# SCH_Sherap_2021-11-23.net
KiCad netlist of a schematic drawn in EasyEDA
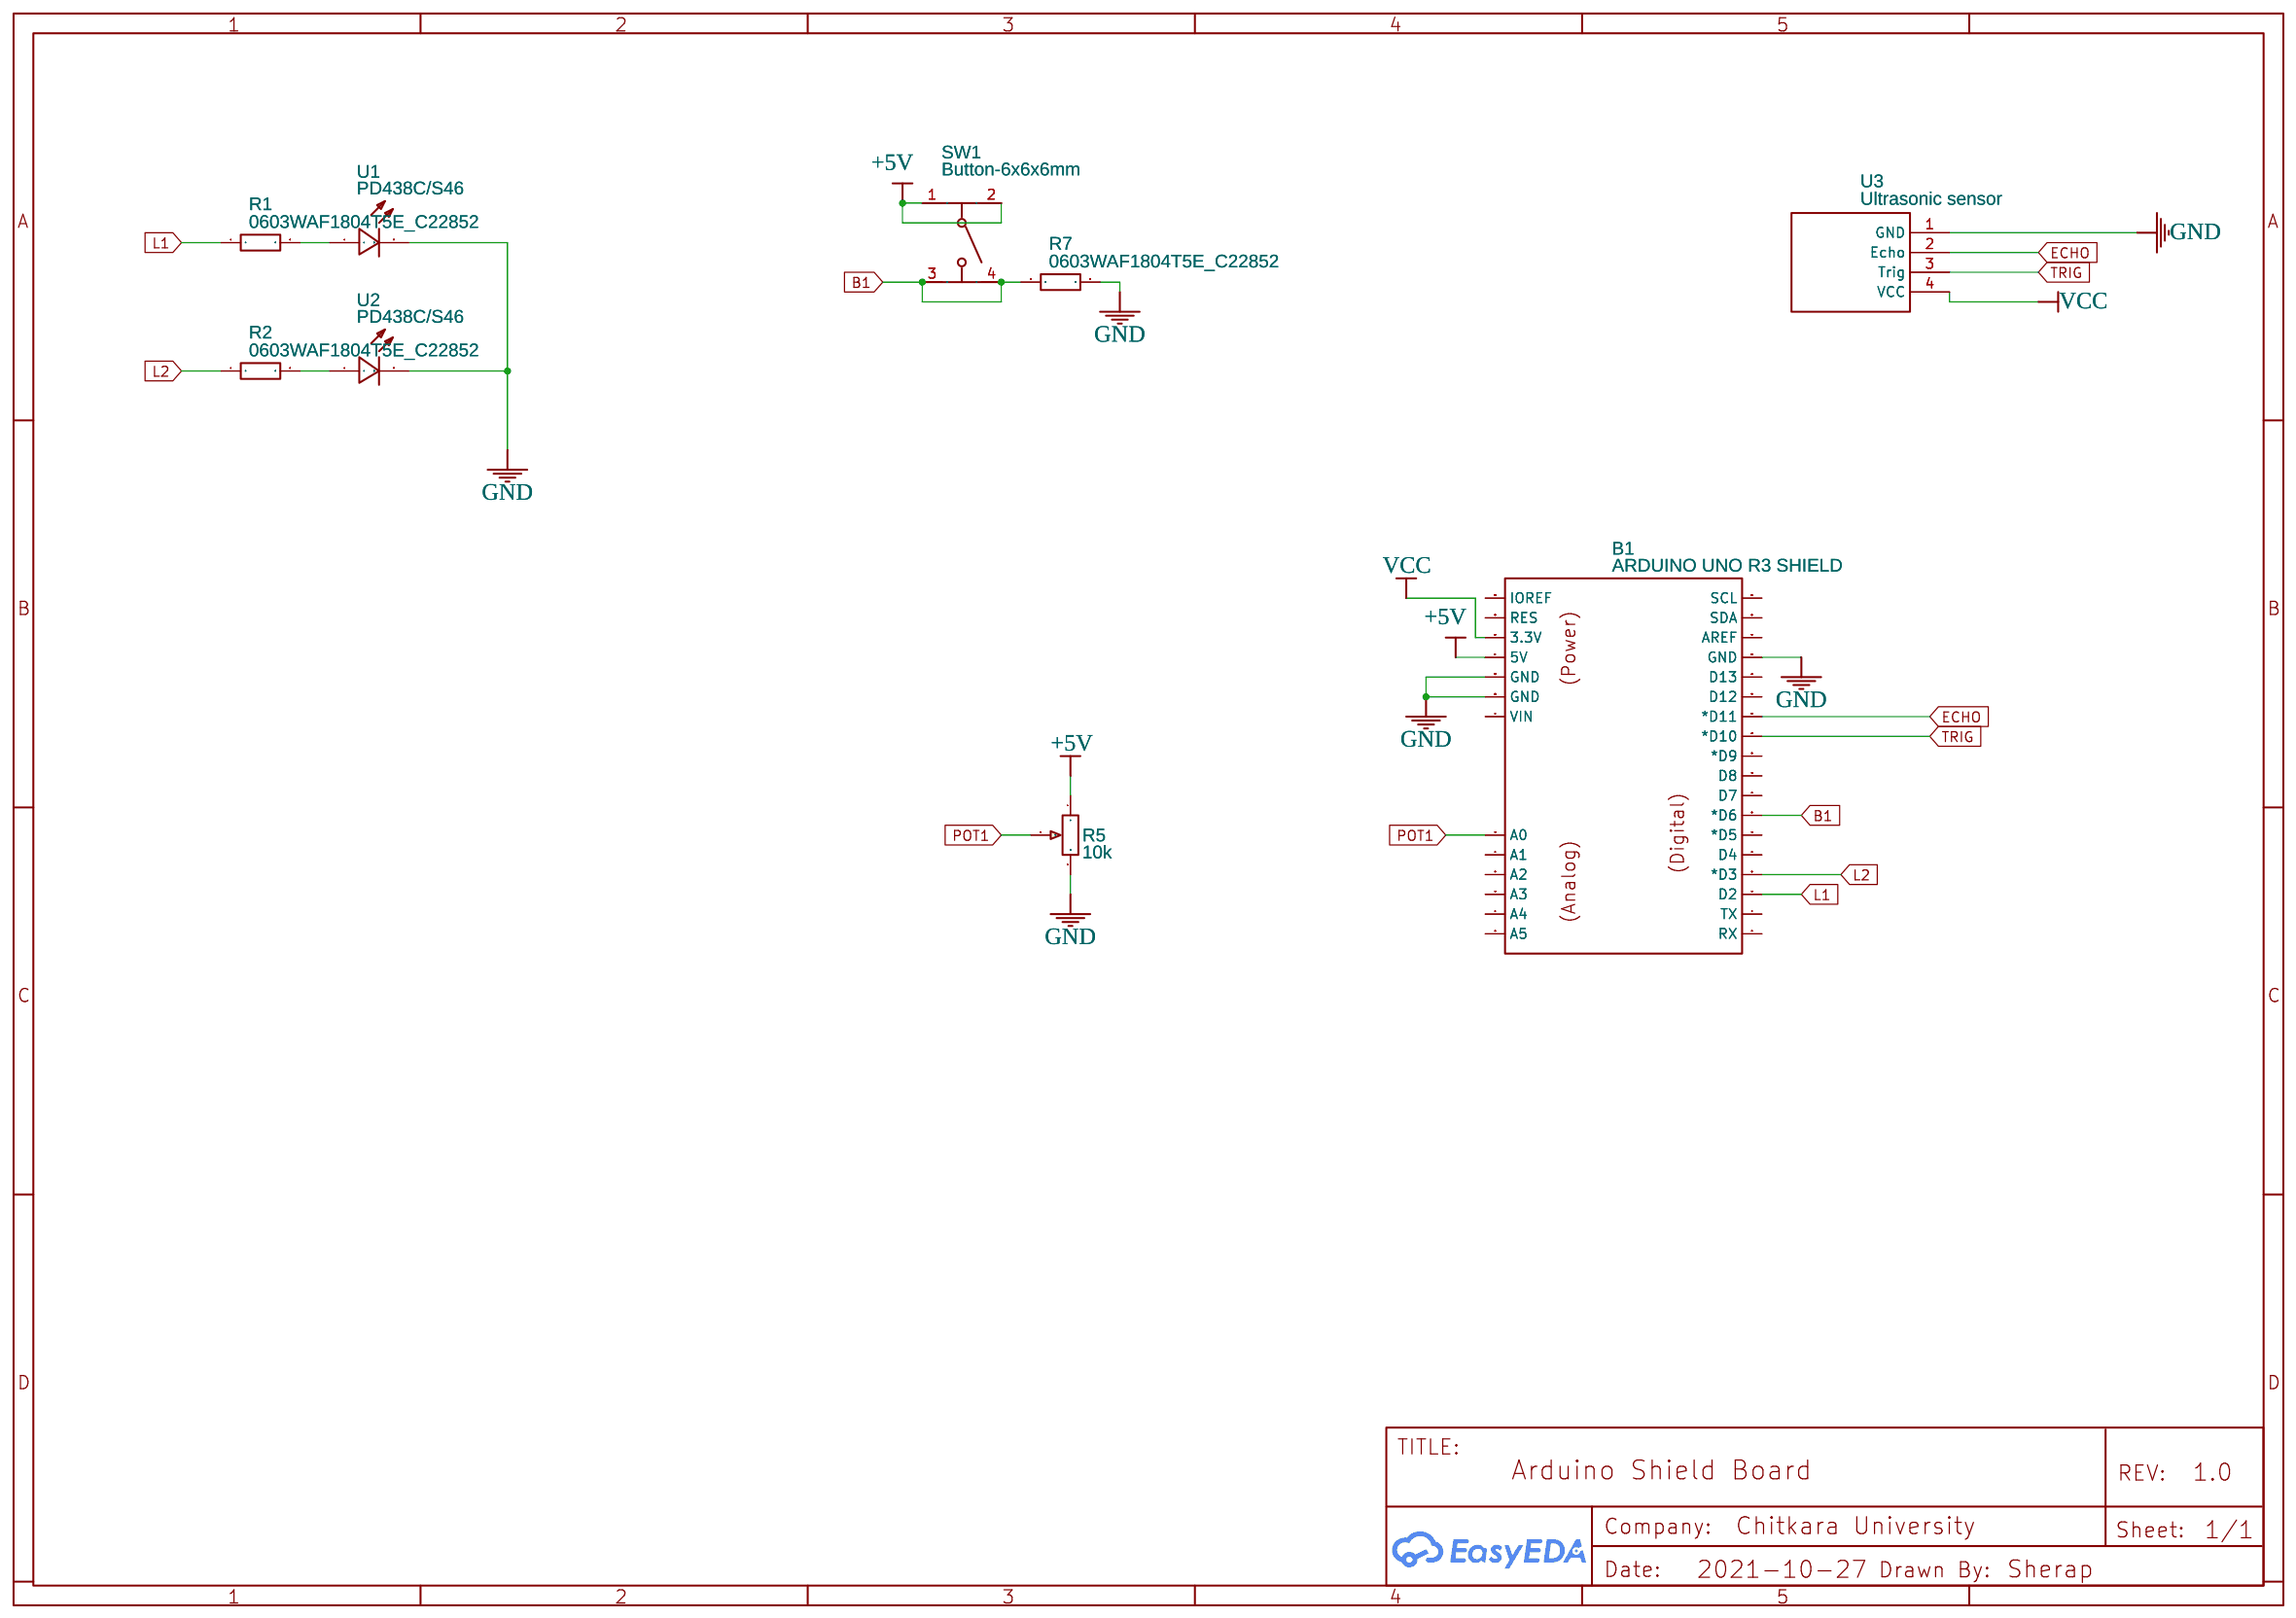
[diagram p0: schematic sheet]

(export (version "E")
  (design (tool "Eeschema 10.0.6"))
  (components
    (comp (ref "B1")
      (value "ARDUINO UNO R3 SHIELD")
      (fields (field (name "Manufacturer") "?"))
      (libsource (lib "") (part "ARDUINO UNO R3 SHIELD"))
    )
    (comp (ref "R1")
      (value "0603WAF1804T5E_C22852")
      (fields
        (field (name "BOM_Manufacturer Part") "0603WAF1804T5E")
        (field (name "BOM_Supplier Part") "C22852")
      )
      (libsource (lib "") (part "0603WAF1804T5E_C22852"))
    )
    (comp (ref "R2")
      (value "0603WAF1804T5E_C22852")
      (fields
        (field (name "BOM_Manufacturer Part") "0603WAF1804T5E")
        (field (name "BOM_Supplier Part") "C22852")
      )
      (libsource (lib "") (part "0603WAF1804T5E_C22852"))
    )
    (comp (ref "R5")
      (value "10k")
      (fields
        (field (name "BOM_Manufacturer Part") "3362F-1-103LF")
        (field (name "BOM_Supplier Part") "3362F-1-103LF-ND")
      )
      (libsource (lib "") (part "3362F-1-103LF"))
    )
    (comp (ref "R7")
      (value "0603WAF1804T5E_C22852")
      (fields
        (field (name "BOM_Manufacturer Part") "0603WAF1804T5E")
        (field (name "BOM_Supplier Part") "C22852")
      )
      (libsource (lib "") (part "0603WAF1804T5E_C22852"))
    )
    (comp (ref "SW1")
      (value "Button-6x6x6mm")
      (fields
        (field (name "BOM_Manufacturer Part") "Switch,6*6*6Plastic head,260G, 0.25mm,Straight line")
        (field (name "BOM_Supplier Part") "C71836")
      )
      (libsource (lib "") (part "Button-6x6x6mm"))
    )
    (comp (ref "U1")
      (value "PD438C/S46")
      (fields (field (name "BOM_Supplier Part") "C146238"))
      (libsource (lib "") (part "PD438C/S46"))
    )
    (comp (ref "U2")
      (value "PD438C/S46")
      (fields (field (name "BOM_Supplier Part") "C146238"))
      (libsource (lib "") (part "PD438C/S46"))
    )
    (comp (ref "U3") (value "Ultrasonic sensor") (libsource (lib "") (part "Ultrasonic sensor")))
  )
  (nets
    (net (code "1") (name "+5V") (class "Default")
      (node (ref "B1") (pin "5V") (pinfunction "5V_5V") (pintype "unspecified"))
      (node (ref "R5") (pin "1") (pinfunction "1_1") (pintype "input"))
      (node (ref "SW1") (pin "1") (pinfunction "1_1") (pintype "unspecified"))
      (node (ref "SW1") (pin "2") (pinfunction "2_2") (pintype "unspecified"))
    )
    (net (code "2") (name "B1") (class "Default")
      (node (ref "B1") (pin "D6") (pinfunction "*D6_D6") (pintype "unspecified"))
      (node (ref "R7") (pin "1") (pinfunction "1_1") (pintype "input"))
      (node (ref "SW1") (pin "3") (pinfunction "3_3") (pintype "unspecified"))
      (node (ref "SW1") (pin "4") (pinfunction "4_4") (pintype "unspecified"))
    )
    (net (code "3") (name "ECHO") (class "Default")
      (node (ref "B1") (pin "D11") (pinfunction "*D11_D11") (pintype "unspecified"))
      (node (ref "U3") (pin "2") (pinfunction "Echo_2") (pintype "unspecified"))
    )
    (net (code "4") (name "GND") (class "Default")
      (node (ref "B1") (pin "GND@0") (pinfunction "GND_GND@0") (pintype "unspecified"))
      (node (ref "B1") (pin "GND@1") (pinfunction "GND_GND@1") (pintype "unspecified"))
      (node (ref "B1") (pin "GND@2") (pinfunction "GND_GND@2") (pintype "unspecified"))
      (node (ref "R5") (pin "3") (pinfunction "3_3") (pintype "input"))
      (node (ref "R7") (pin "2") (pinfunction "2_2") (pintype "input"))
      (node (ref "U1") (pin "2") (pinfunction "C_2") (pintype "unspecified"))
      (node (ref "U2") (pin "2") (pinfunction "C_2") (pintype "unspecified"))
      (node (ref "U3") (pin "1") (pinfunction "GND_1") (pintype "unspecified"))
    )
    (net (code "5") (name "L1") (class "Default")
      (node (ref "B1") (pin "D2") (pinfunction "D2_D2") (pintype "unspecified"))
      (node (ref "R1") (pin "1") (pinfunction "1_1") (pintype "input"))
    )
    (net (code "6") (name "L2") (class "Default")
      (node (ref "B1") (pin "D3") (pinfunction "*D3_D3") (pintype "unspecified"))
      (node (ref "R2") (pin "1") (pinfunction "1_1") (pintype "input"))
    )
    (net (code "7") (name "Net-(U1-A)") (class "Default")
      (node (ref "R1") (pin "2") (pinfunction "2_2") (pintype "input"))
      (node (ref "U1") (pin "1") (pinfunction "A_1") (pintype "unspecified"))
    )
    (net (code "8") (name "Net-(U2-A)") (class "Default")
      (node (ref "R2") (pin "2") (pinfunction "2_2") (pintype "input"))
      (node (ref "U2") (pin "1") (pinfunction "A_1") (pintype "unspecified"))
    )
    (net (code "9") (name "POT1") (class "Default")
      (node (ref "B1") (pin "A0") (pinfunction "A0_A0") (pintype "unspecified"))
      (node (ref "R5") (pin "2") (pinfunction "2_2") (pintype "input"))
    )
    (net (code "10") (name "TRIG") (class "Default")
      (node (ref "B1") (pin "D10") (pinfunction "*D10_D10") (pintype "unspecified"))
      (node (ref "U3") (pin "3") (pinfunction "Trig_3") (pintype "unspecified"))
    )
    (net (code "11") (name "VCC") (class "Default")
      (node (ref "B1") (pin "3.3V") (pinfunction "3.3V_3.3V") (pintype "unspecified"))
      (node (ref "U3") (pin "4") (pinfunction "VCC_4") (pintype "unspecified"))
    )
    (net (code "12") (name "unconnected-(B1-*D5-PadD5)") (class "Default")
      (node (ref "B1") (pin "D5") (pinfunction "*D5_D5") (pintype "unspecified"))
    )
    (net (code "13") (name "unconnected-(B1-*D9-PadD9)") (class "Default")
      (node (ref "B1") (pin "D9") (pinfunction "*D9_D9") (pintype "unspecified"))
    )
    (net (code "14") (name "unconnected-(B1-PadA1)") (class "Default")
      (node (ref "B1") (pin "A1") (pinfunction "A1_A1") (pintype "unspecified"))
    )
    (net (code "15") (name "unconnected-(B1-PadA2)") (class "Default")
      (node (ref "B1") (pin "A2") (pinfunction "A2_A2") (pintype "unspecified"))
    )
    (net (code "16") (name "unconnected-(B1-PadA3)") (class "Default")
      (node (ref "B1") (pin "A3") (pinfunction "A3_A3") (pintype "unspecified"))
    )
    (net (code "17") (name "unconnected-(B1-PadA4)") (class "Default")
      (node (ref "B1") (pin "A4") (pinfunction "A4_A4") (pintype "unspecified"))
    )
    (net (code "18") (name "unconnected-(B1-PadA5)") (class "Default")
      (node (ref "B1") (pin "A5") (pinfunction "A5_A5") (pintype "unspecified"))
    )
    (net (code "19") (name "unconnected-(B1-PadAREF)") (class "Default")
      (node (ref "B1") (pin "AREF") (pinfunction "AREF_AREF") (pintype "unspecified"))
    )
    (net (code "20") (name "unconnected-(B1-PadD4)") (class "Default")
      (node (ref "B1") (pin "D4") (pinfunction "D4_D4") (pintype "unspecified"))
    )
    (net (code "21") (name "unconnected-(B1-PadD7)") (class "Default")
      (node (ref "B1") (pin "D7") (pinfunction "D7_D7") (pintype "unspecified"))
    )
    (net (code "22") (name "unconnected-(B1-PadD8)") (class "Default")
      (node (ref "B1") (pin "D8") (pinfunction "D8_D8") (pintype "unspecified"))
    )
    (net (code "23") (name "unconnected-(B1-PadD12)") (class "Default")
      (node (ref "B1") (pin "D12") (pinfunction "D12_D12") (pintype "unspecified"))
    )
    (net (code "24") (name "unconnected-(B1-PadD13)") (class "Default")
      (node (ref "B1") (pin "D13") (pinfunction "D13_D13") (pintype "unspecified"))
    )
    (net (code "25") (name "unconnected-(B1-PadIOREF)") (class "Default")
      (node (ref "B1") (pin "IOREF") (pinfunction "IOREF_IOREF") (pintype "unspecified"))
    )
    (net (code "26") (name "unconnected-(B1-PadRES)") (class "Default")
      (node (ref "B1") (pin "RES") (pinfunction "RES_RES") (pintype "unspecified"))
    )
    (net (code "27") (name "unconnected-(B1-PadRX)") (class "Default")
      (node (ref "B1") (pin "RX") (pinfunction "RX_RX") (pintype "unspecified"))
    )
    (net (code "28") (name "unconnected-(B1-PadSCL)") (class "Default")
      (node (ref "B1") (pin "SCL") (pinfunction "SCL_SCL") (pintype "unspecified"))
    )
    (net (code "29") (name "unconnected-(B1-PadSDA)") (class "Default")
      (node (ref "B1") (pin "SDA") (pinfunction "SDA_SDA") (pintype "unspecified"))
    )
    (net (code "30") (name "unconnected-(B1-PadTX)") (class "Default")
      (node (ref "B1") (pin "TX") (pinfunction "TX_TX") (pintype "unspecified"))
    )
    (net (code "31") (name "unconnected-(B1-PadVIN)") (class "Default")
      (node (ref "B1") (pin "VIN") (pinfunction "VIN_VIN") (pintype "unspecified"))
    )
  )
)
